# mainboard_v3.net
KiCad netlist of a schematic drawn in EAGLE
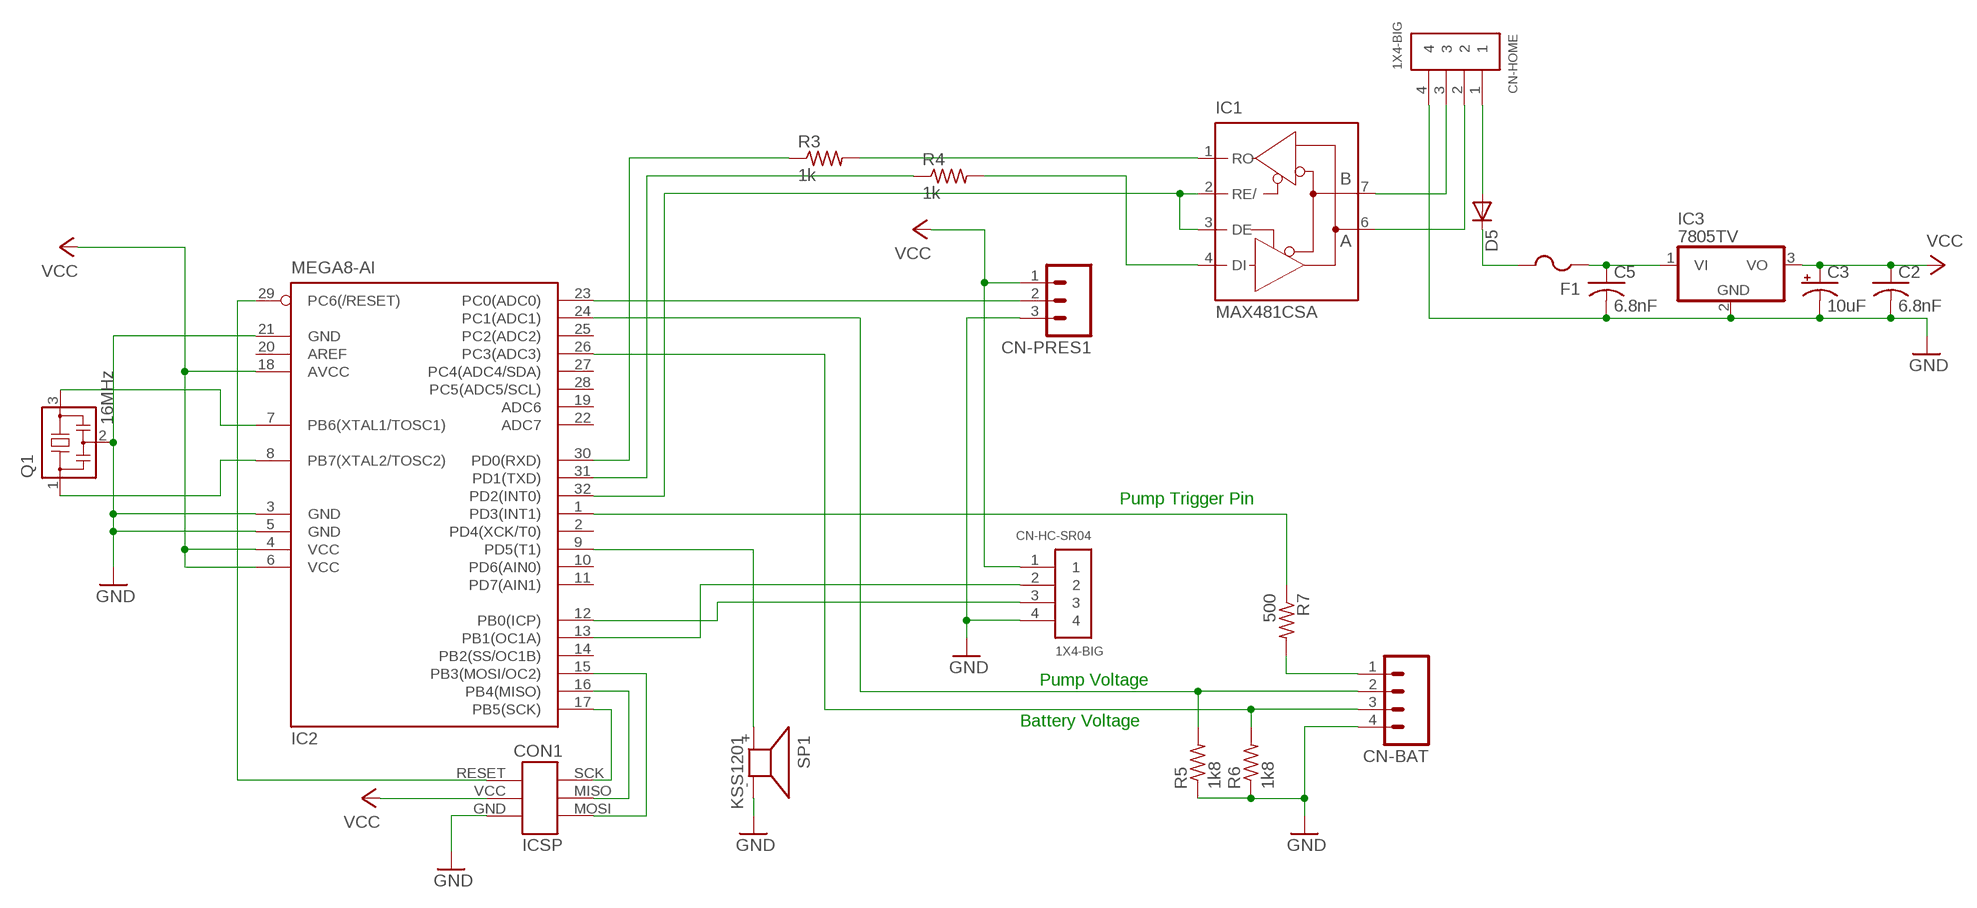
[diagram p0: schematic, sheet 1]

(export (version "E")
  (design (tool "Eeschema 10.0.6"))
  (components
    (comp (ref "C2")
      (value "6.8nF")
      (footprint "eagle-import:C050-024X044")
      (libsource (lib "eagle-import") (part "C-US050-024X044"))
    )
    (comp (ref "C3")
      (value "10uF")
      (footprint "eagle-import:E1,8-4")
      (libsource (lib "eagle-import") (part "CPOL-USE1.8-4"))
    )
    (comp (ref "C5")
      (value "6.8nF")
      (footprint "eagle-import:C050-024X044")
      (libsource (lib "eagle-import") (part "C-US050-024X044"))
    )
    (comp (ref "CN-BAT")
      (value "M04")
      (footprint "eagle-import:04P")
      (libsource (lib "eagle-import") (part "M04"))
    )
    (comp (ref "CN-HC-SR04")
      (value "1X4-BIG")
      (footprint "eagle-import:1X04-BIG")
      (libsource (lib "eagle-import") (part "1X4-BIG"))
    )
    (comp (ref "CN-HOME")
      (value "1X4-BIG")
      (footprint "eagle-import:1X04-BIG")
      (libsource (lib "eagle-import") (part "1X4-BIG"))
    )
    (comp (ref "CN-PRES1")
      (value "M03")
      (footprint "eagle-import:03P")
      (libsource (lib "eagle-import") (part "M03"))
    )
    (comp (ref "CON1")
      (value "ICSP-HEADER")
      (footprint "eagle-import:ICSP-HEADER")
      (libsource (lib "eagle-import") (part "ICSP-HEADER"))
    )
    (comp (ref "D5")
      (value "DIODE-MICROMELF-W")
      (footprint "eagle-import:MICROMELF-W")
      (libsource (lib "eagle-import") (part "DIODE-MICROMELF-W"))
    )
    (comp (ref "F1")
      (value "PTCFUSE-1206")
      (footprint "eagle-import:R1206")
      (libsource (lib "eagle-import") (part "PTCFUSE-1206"))
    )
    (comp (ref "IC1")
      (value "MAX481CSA")
      (footprint "eagle-import:SO08")
      (fields (field (name "MF") "MAXIM"))
      (libsource (lib "eagle-import") (part "MAX481CSA"))
    )
    (comp (ref "IC2")
      (value "MEGA8-AI")
      (footprint "eagle-import:TQFP32-08")
      (fields (field (name "MPN") "ATMEGA8-16AU"))
      (libsource (lib "eagle-import") (part "MEGA8-AI"))
    )
    (comp (ref "IC3")
      (value "7805TV")
      (footprint "eagle-import:TO220V")
      (libsource (lib "eagle-import") (part "78TV05"))
    )
    (comp (ref "Q1")
      (value "16MHz")
      (footprint "eagle-import:RESONATOR")
      (libsource (lib "eagle-import") (part "RESONATOR"))
    )
    (comp (ref "R3")
      (value "1k")
      (footprint "eagle-import:R0603")
      (libsource (lib "eagle-import") (part "R-US_R0603"))
    )
    (comp (ref "R4")
      (value "1k")
      (footprint "eagle-import:R0603")
      (libsource (lib "eagle-import") (part "R-US_R0603"))
    )
    (comp (ref "R5")
      (value "1k8")
      (footprint "eagle-import:R0603")
      (libsource (lib "eagle-import") (part "R-US_R0603"))
    )
    (comp (ref "R6")
      (value "1k8")
      (footprint "eagle-import:R0603")
      (libsource (lib "eagle-import") (part "R-US_R0603"))
    )
    (comp (ref "R7")
      (value "500")
      (footprint "eagle-import:R0603")
      (libsource (lib "eagle-import") (part "R-US_R0603"))
    )
    (comp (ref "SP1")
      (value "KSS1201")
      (footprint "eagle-import:KSS1201")
      (libsource (lib "eagle-import") (part "KSS1201"))
    )
  )
  (nets
    (net (code "1") (name "GND") (class "Default")
      (node (ref "C2") (pin "2") (pinfunction "2_2") (pintype "passive"))
      (node (ref "C3") (pin "-") (pinfunction "-_-") (pintype "passive"))
      (node (ref "C5") (pin "2") (pinfunction "2_2") (pintype "passive"))
      (node (ref "CN-BAT") (pin "4") (pinfunction "4_4") (pintype "passive"))
      (node (ref "CN-HC-SR04") (pin "4") (pinfunction "4_4") (pintype "bidirectional"))
      (node (ref "CN-HOME") (pin "4") (pinfunction "4_4") (pintype "bidirectional"))
      (node (ref "CN-PRES1") (pin "3") (pinfunction "3_3") (pintype "passive"))
      (node (ref "CON1") (pin "GND") (pinfunction "GND_GND") (pintype "bidirectional"))
      (node (ref "IC2") (pin "21") (pinfunction "GND_21") (pintype "power_in"))
      (node (ref "IC2") (pin "3") (pinfunction "GND_3") (pintype "power_in"))
      (node (ref "IC2") (pin "5") (pinfunction "GND_5") (pintype "power_in"))
      (node (ref "IC3") (pin "2") (pinfunction "GND_2") (pintype "passive"))
      (node (ref "Q1") (pin "2") (pinfunction "2_2") (pintype "passive"))
      (node (ref "R5") (pin "1") (pinfunction "1_1") (pintype "passive"))
      (node (ref "R6") (pin "1") (pinfunction "1_1") (pintype "passive"))
      (node (ref "SP1") (pin "-") (pinfunction "2_-") (pintype "passive"))
    )
    (net (code "2") (name "Net-(CN-BAT-Pad1)") (class "Default")
      (node (ref "CN-BAT") (pin "1") (pinfunction "1_1") (pintype "passive"))
      (node (ref "R7") (pin "2") (pinfunction "2_2") (pintype "passive"))
    )
    (net (code "3") (name "Net-(CN-HOME-Pad1)") (class "Default")
      (node (ref "CN-HOME") (pin "1") (pinfunction "1_1") (pintype "bidirectional"))
      (node (ref "D5") (pin "A") (pinfunction "A_A") (pintype "passive"))
    )
    (net (code "4") (name "Net-(D5-PadC)") (class "Default")
      (node (ref "D5") (pin "C") (pinfunction "C_C") (pintype "passive"))
      (node (ref "F1") (pin "2") (pinfunction "2_2") (pintype "passive"))
    )
    (net (code "5") (name "Net-(IC1A-A)") (class "Default")
      (node (ref "CN-HOME") (pin "2") (pinfunction "2_2") (pintype "bidirectional"))
      (node (ref "IC1") (pin "6") (pinfunction "A_6") (pintype "passive"))
    )
    (net (code "6") (name "Net-(IC1A-B)") (class "Default")
      (node (ref "CN-HOME") (pin "3") (pinfunction "3_3") (pintype "bidirectional"))
      (node (ref "IC1") (pin "7") (pinfunction "B_7") (pintype "passive"))
    )
    (net (code "7") (name "Net-(IC1A-DE)") (class "Default")
      (node (ref "IC1") (pin "2") (pinfunction "RE/_2") (pintype "input"))
      (node (ref "IC1") (pin "3") (pinfunction "DE_3") (pintype "input"))
      (node (ref "IC2") (pin "32") (pinfunction "PD2(INT0)_32") (pintype "bidirectional"))
    )
    (net (code "8") (name "Net-(IC1A-DI)") (class "Default")
      (node (ref "IC1") (pin "4") (pinfunction "DI_4") (pintype "input"))
      (node (ref "R4") (pin "2") (pinfunction "2_2") (pintype "passive"))
    )
    (net (code "9") (name "Net-(IC1A-RO)") (class "Default")
      (node (ref "IC1") (pin "1") (pinfunction "RO_1") (pintype "output"))
      (node (ref "R3") (pin "2") (pinfunction "2_2") (pintype "passive"))
    )
    (net (code "10") (name "Net-(IC2-PB0(ICP))") (class "Default")
      (node (ref "CN-HC-SR04") (pin "3") (pinfunction "3_3") (pintype "bidirectional"))
      (node (ref "IC2") (pin "12") (pinfunction "PB0(ICP)_12") (pintype "bidirectional"))
    )
    (net (code "11") (name "Net-(IC2-PB1(OC1A))") (class "Default")
      (node (ref "CN-HC-SR04") (pin "2") (pinfunction "2_2") (pintype "bidirectional"))
      (node (ref "IC2") (pin "13") (pinfunction "PB1(OC1A)_13") (pintype "bidirectional"))
    )
    (net (code "12") (name "Net-(IC2-PB3(MOSI{slash}OC2))") (class "Default")
      (node (ref "CON1") (pin "MOSI") (pinfunction "MOSI_MOSI") (pintype "bidirectional"))
      (node (ref "IC2") (pin "15") (pinfunction "PB3(MOSI/OC2)_15") (pintype "bidirectional"))
    )
    (net (code "13") (name "Net-(IC2-PB4(MISO))") (class "Default")
      (node (ref "CON1") (pin "MISO") (pinfunction "MISO_MISO") (pintype "bidirectional"))
      (node (ref "IC2") (pin "16") (pinfunction "PB4(MISO)_16") (pintype "bidirectional"))
    )
    (net (code "14") (name "Net-(IC2-PB5(SCK))") (class "Default")
      (node (ref "CON1") (pin "SCK") (pinfunction "SCK_SCK") (pintype "bidirectional"))
      (node (ref "IC2") (pin "17") (pinfunction "PB5(SCK)_17") (pintype "bidirectional"))
    )
    (net (code "15") (name "Net-(IC2-PB6(XTAL1{slash}TOSC1))") (class "Default")
      (node (ref "IC2") (pin "7") (pinfunction "PB6(XTAL1/TOSC1)_7") (pintype "bidirectional"))
      (node (ref "Q1") (pin "3") (pinfunction "3_3") (pintype "passive"))
    )
    (net (code "16") (name "Net-(IC2-PB7(XTAL2{slash}TOSC2))") (class "Default")
      (node (ref "IC2") (pin "8") (pinfunction "PB7(XTAL2/TOSC2)_8") (pintype "bidirectional"))
      (node (ref "Q1") (pin "1") (pinfunction "1_1") (pintype "passive"))
    )
    (net (code "17") (name "Net-(IC2-PC0(ADC0))") (class "Default")
      (node (ref "CN-PRES1") (pin "2") (pinfunction "2_2") (pintype "passive"))
      (node (ref "IC2") (pin "23") (pinfunction "PC0(ADC0)_23") (pintype "bidirectional"))
    )
    (net (code "18") (name "Net-(IC2-PC1(ADC1))") (class "Default")
      (node (ref "CN-BAT") (pin "2") (pinfunction "2_2") (pintype "passive"))
      (node (ref "IC2") (pin "24") (pinfunction "PC1(ADC1)_24") (pintype "bidirectional"))
      (node (ref "R5") (pin "2") (pinfunction "2_2") (pintype "passive"))
    )
    (net (code "19") (name "Net-(IC2-PC3(ADC3))") (class "Default")
      (node (ref "CN-BAT") (pin "3") (pinfunction "3_3") (pintype "passive"))
      (node (ref "IC2") (pin "26") (pinfunction "PC3(ADC3)_26") (pintype "bidirectional"))
      (node (ref "R6") (pin "2") (pinfunction "2_2") (pintype "passive"))
    )
    (net (code "20") (name "Net-(IC2-PC6({slash}RESET))") (class "Default")
      (node (ref "CON1") (pin "RESET") (pinfunction "RESET_RESET") (pintype "bidirectional"))
      (node (ref "IC2") (pin "29") (pinfunction "PC6(/RESET)_29") (pintype "bidirectional"))
    )
    (net (code "21") (name "Net-(IC2-PD0(RXD))") (class "Default")
      (node (ref "IC2") (pin "30") (pinfunction "PD0(RXD)_30") (pintype "bidirectional"))
      (node (ref "R3") (pin "1") (pinfunction "1_1") (pintype "passive"))
    )
    (net (code "22") (name "Net-(IC2-PD1(TXD))") (class "Default")
      (node (ref "IC2") (pin "31") (pinfunction "PD1(TXD)_31") (pintype "bidirectional"))
      (node (ref "R4") (pin "1") (pinfunction "1_1") (pintype "passive"))
    )
    (net (code "23") (name "Net-(IC2-PD3(INT1))") (class "Default")
      (node (ref "IC2") (pin "1") (pinfunction "PD3(INT1)_1") (pintype "bidirectional"))
      (node (ref "R7") (pin "1") (pinfunction "1_1") (pintype "passive"))
    )
    (net (code "24") (name "Net-(IC2-PD5(T1))") (class "Default")
      (node (ref "IC2") (pin "9") (pinfunction "PD5(T1)_9") (pintype "bidirectional"))
      (node (ref "SP1") (pin "+") (pinfunction "1_+") (pintype "passive"))
    )
    (net (code "25") (name "Net-(IC3-VI)") (class "Default")
      (node (ref "C5") (pin "1") (pinfunction "1_1") (pintype "passive"))
      (node (ref "F1") (pin "1") (pinfunction "1_1") (pintype "passive"))
      (node (ref "IC3") (pin "1") (pinfunction "VI_1") (pintype "input"))
    )
    (net (code "26") (name "VCC") (class "Default")
      (node (ref "C2") (pin "1") (pinfunction "1_1") (pintype "passive"))
      (node (ref "C3") (pin "+") (pinfunction "+_+") (pintype "passive"))
      (node (ref "CN-HC-SR04") (pin "1") (pinfunction "1_1") (pintype "bidirectional"))
      (node (ref "CN-PRES1") (pin "1") (pinfunction "1_1") (pintype "passive"))
      (node (ref "CON1") (pin "VCC") (pinfunction "+5V_VCC") (pintype "bidirectional"))
      (node (ref "IC2") (pin "18") (pinfunction "AVCC_18") (pintype "power_in"))
      (node (ref "IC2") (pin "4") (pinfunction "VCC_4") (pintype "power_in"))
      (node (ref "IC2") (pin "6") (pinfunction "VCC_6") (pintype "power_in"))
      (node (ref "IC3") (pin "3") (pinfunction "VO_3") (pintype "passive"))
    )
    (net (code "27") (name "unconnected-(IC2-ADC6-Pad19)") (class "Default")
      (node (ref "IC2") (pin "19") (pinfunction "ADC6_19") (pintype "bidirectional"))
    )
    (net (code "28") (name "unconnected-(IC2-ADC7-Pad22)") (class "Default")
      (node (ref "IC2") (pin "22") (pinfunction "ADC7_22") (pintype "bidirectional"))
    )
    (net (code "29") (name "unconnected-(IC2-AREF-Pad20)") (class "Default")
      (node (ref "IC2") (pin "20") (pinfunction "AREF_20") (pintype "passive"))
    )
    (net (code "30") (name "unconnected-(IC2-PB2(SS{slash}OC1B)-Pad14)") (class "Default")
      (node (ref "IC2") (pin "14") (pinfunction "PB2(SS/OC1B)_14") (pintype "bidirectional"))
    )
    (net (code "31") (name "unconnected-(IC2-PC2(ADC2)-Pad25)") (class "Default")
      (node (ref "IC2") (pin "25") (pinfunction "PC2(ADC2)_25") (pintype "bidirectional"))
    )
    (net (code "32") (name "unconnected-(IC2-PC4(ADC4{slash}SDA)-Pad27)") (class "Default")
      (node (ref "IC2") (pin "27") (pinfunction "PC4(ADC4/SDA)_27") (pintype "bidirectional"))
    )
    (net (code "33") (name "unconnected-(IC2-PC5(ADC5{slash}SCL)-Pad28)") (class "Default")
      (node (ref "IC2") (pin "28") (pinfunction "PC5(ADC5/SCL)_28") (pintype "bidirectional"))
    )
    (net (code "34") (name "unconnected-(IC2-PD4(XCK{slash}T0)-Pad2)") (class "Default")
      (node (ref "IC2") (pin "2") (pinfunction "PD4(XCK/T0)_2") (pintype "bidirectional"))
    )
    (net (code "35") (name "unconnected-(IC2-PD6(AIN0)-Pad10)") (class "Default")
      (node (ref "IC2") (pin "10") (pinfunction "PD6(AIN0)_10") (pintype "bidirectional"))
    )
    (net (code "36") (name "unconnected-(IC2-PD7(AIN1)-Pad11)") (class "Default")
      (node (ref "IC2") (pin "11") (pinfunction "PD7(AIN1)_11") (pintype "bidirectional"))
    )
  )
)
